# untitled.net
KiCad netlist of a schematic drawn in EAGLE
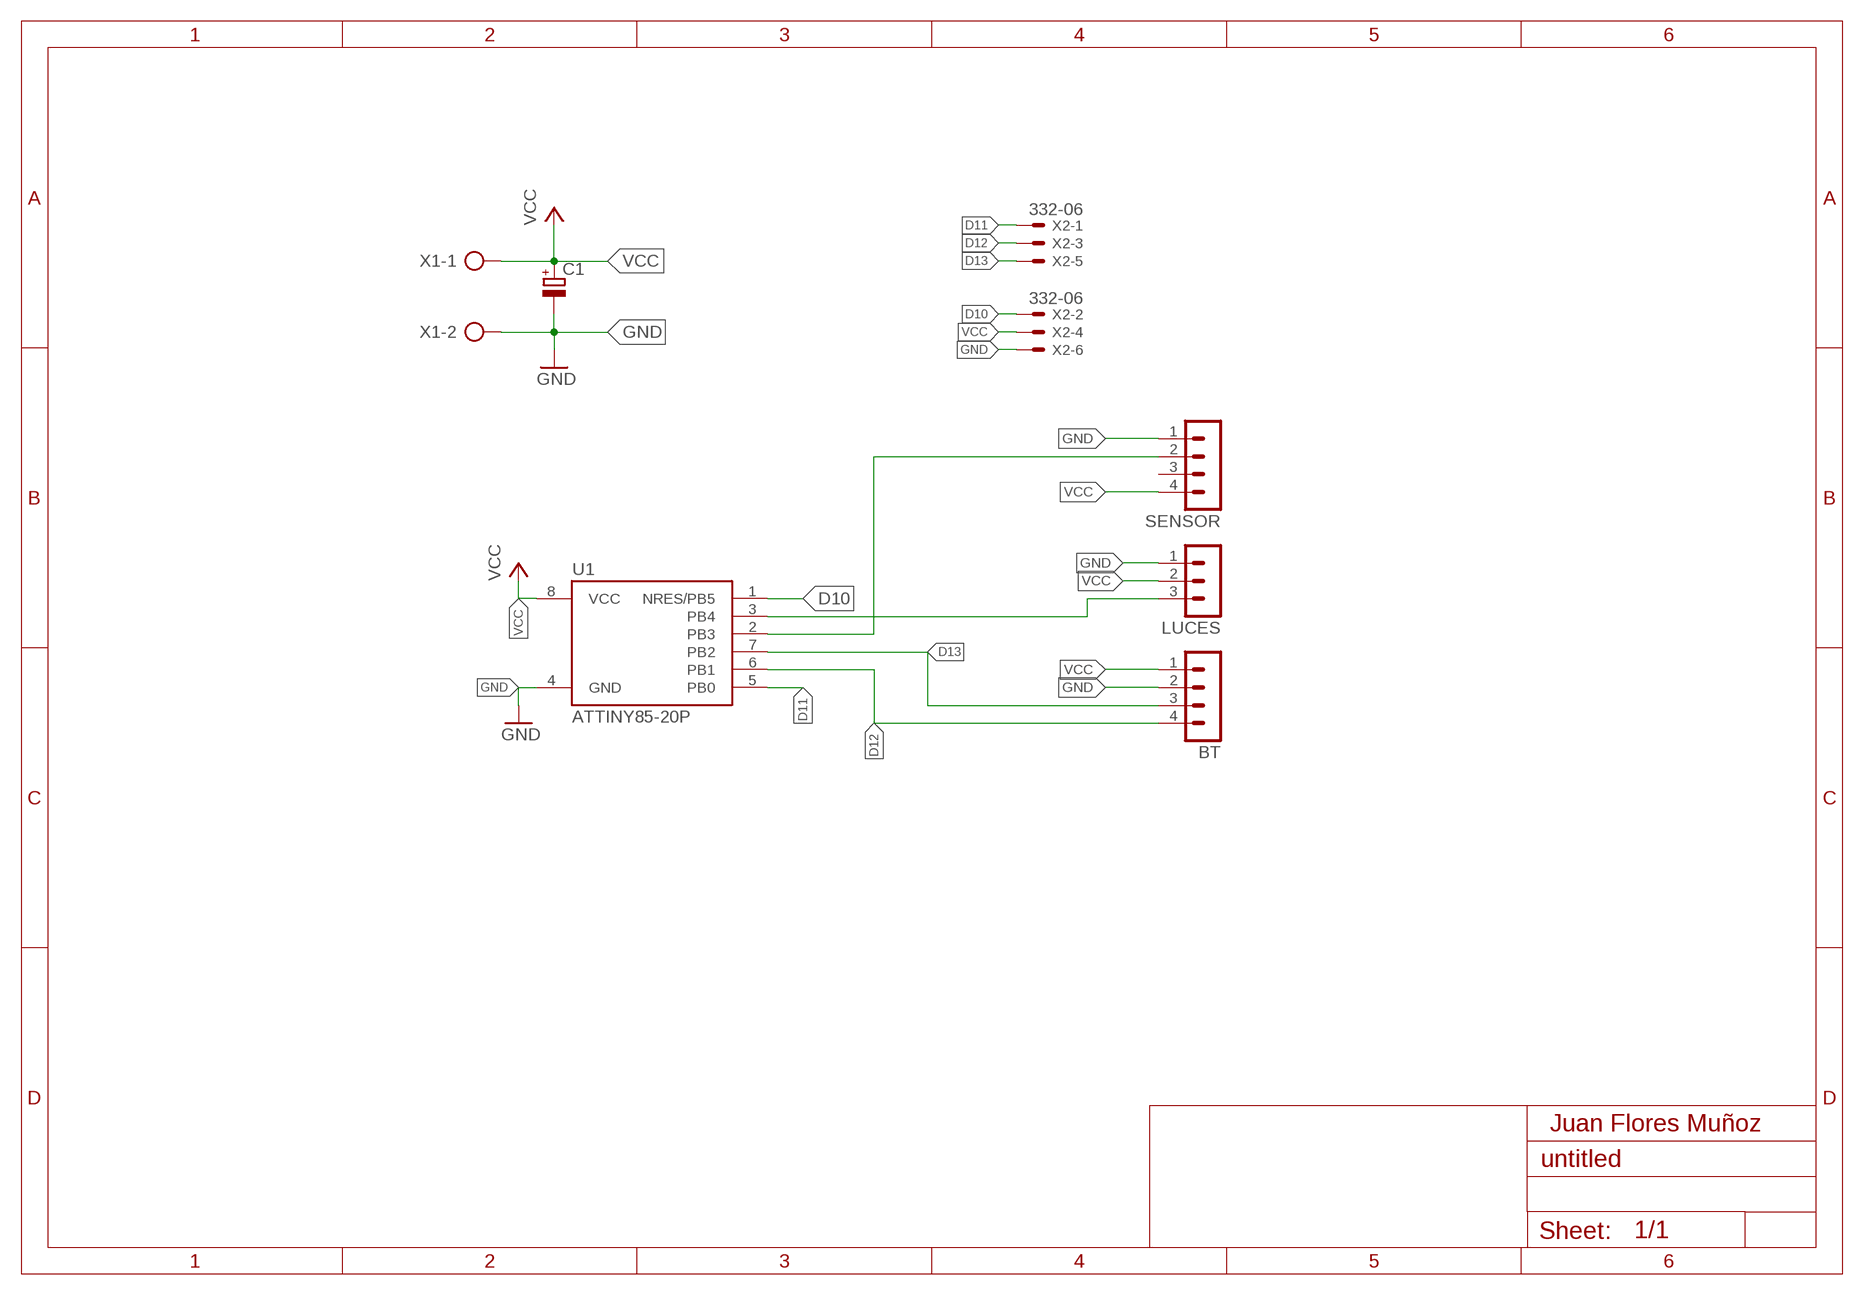
[diagram p0: schematic, sheet 1]

(export (version "E")
  (design (tool "Eeschema 10.0.6"))
  (components
    (comp (ref "BT")
      (value "MA04-1")
      (footprint "eagle-import:MA04-1")
      (libsource (lib "eagle-import") (part "MA04-1"))
    )
    (comp (ref "C1")
      (value "CPOL-EUE2,5-6E")
      (footprint "eagle-import:E2,5-6E")
      (libsource (lib "eagle-import") (part "CPOL-EUE2,5-6E"))
    )
    (comp (ref "LUCES")
      (value "MA03-1")
      (footprint "eagle-import:MA03-1")
      (libsource (lib "eagle-import") (part "MA03-1"))
    )
    (comp (ref "SENSOR")
      (value "MA04-1")
      (footprint "eagle-import:MA04-1")
      (libsource (lib "eagle-import") (part "MA04-1"))
    )
    (comp (ref "U1")
      (value "ATTINY85-20P")
      (footprint "eagle-import:PDIP08_300MIL")
      (libsource (lib "eagle-import") (part "ATTINY85P-20"))
    )
    (comp (ref "X1")
      (value "AK500/2")
      (footprint "eagle-import:AK500_2")
      (libsource (lib "eagle-import") (part "AK500/2"))
    )
    (comp (ref "X2")
      (value "332-06")
      (footprint "eagle-import:332-06")
      (libsource (lib "eagle-import") (part "332-06"))
    )
  )
  (nets
    (net (code "1") (name "D10") (class "Default")
      (node (ref "U1") (pin "1") (pinfunction "NRES/PB5_1") (pintype "bidirectional"))
      (node (ref "X2") (pin "2") (pinfunction "S_2") (pintype "passive"))
    )
    (net (code "2") (name "D11") (class "Default")
      (node (ref "U1") (pin "5") (pinfunction "PB0_5") (pintype "bidirectional"))
      (node (ref "X2") (pin "1") (pinfunction "S_1") (pintype "passive"))
    )
    (net (code "3") (name "D12") (class "Default")
      (node (ref "BT") (pin "4") (pinfunction "4_4") (pintype "passive"))
      (node (ref "U1") (pin "6") (pinfunction "PB1_6") (pintype "bidirectional"))
      (node (ref "X2") (pin "3") (pinfunction "S_3") (pintype "passive"))
    )
    (net (code "4") (name "D13") (class "Default")
      (node (ref "BT") (pin "3") (pinfunction "3_3") (pintype "passive"))
      (node (ref "U1") (pin "7") (pinfunction "PB2_7") (pintype "bidirectional"))
      (node (ref "X2") (pin "5") (pinfunction "S_5") (pintype "passive"))
    )
    (net (code "5") (name "GND") (class "Default")
      (node (ref "BT") (pin "2") (pinfunction "2_2") (pintype "passive"))
      (node (ref "C1") (pin "-") (pinfunction "-_-") (pintype "passive"))
      (node (ref "LUCES") (pin "1") (pinfunction "1_1") (pintype "passive"))
      (node (ref "SENSOR") (pin "1") (pinfunction "1_1") (pintype "passive"))
      (node (ref "U1") (pin "4") (pinfunction "GND_4") (pintype "power_in"))
      (node (ref "X1") (pin "2") (pinfunction "KL_2") (pintype "passive"))
      (node (ref "X2") (pin "6") (pinfunction "S_6") (pintype "passive"))
    )
    (net (code "6") (name "Net-(U1-PB3)") (class "Default")
      (node (ref "SENSOR") (pin "2") (pinfunction "2_2") (pintype "passive"))
      (node (ref "U1") (pin "2") (pinfunction "PB3_2") (pintype "bidirectional"))
    )
    (net (code "7") (name "Net-(U1-PB4)") (class "Default")
      (node (ref "LUCES") (pin "3") (pinfunction "3_3") (pintype "passive"))
      (node (ref "U1") (pin "3") (pinfunction "PB4_3") (pintype "bidirectional"))
    )
    (net (code "8") (name "VCC") (class "Default")
      (node (ref "BT") (pin "1") (pinfunction "1_1") (pintype "passive"))
      (node (ref "C1") (pin "+") (pinfunction "+_+") (pintype "passive"))
      (node (ref "LUCES") (pin "2") (pinfunction "2_2") (pintype "passive"))
      (node (ref "SENSOR") (pin "4") (pinfunction "4_4") (pintype "passive"))
      (node (ref "U1") (pin "8") (pinfunction "VCC_8") (pintype "power_in"))
      (node (ref "X1") (pin "1") (pinfunction "KL_1") (pintype "passive"))
      (node (ref "X2") (pin "4") (pinfunction "S_4") (pintype "passive"))
    )
    (net (code "9") (name "unconnected-(SENSOR-Pad3)") (class "Default")
      (node (ref "SENSOR") (pin "3") (pinfunction "3_3") (pintype "passive"))
    )
  )
)
